# SCH_NFC-Business-Card_2025-01-11.net
KiCad netlist of a schematic drawn in EasyEDA
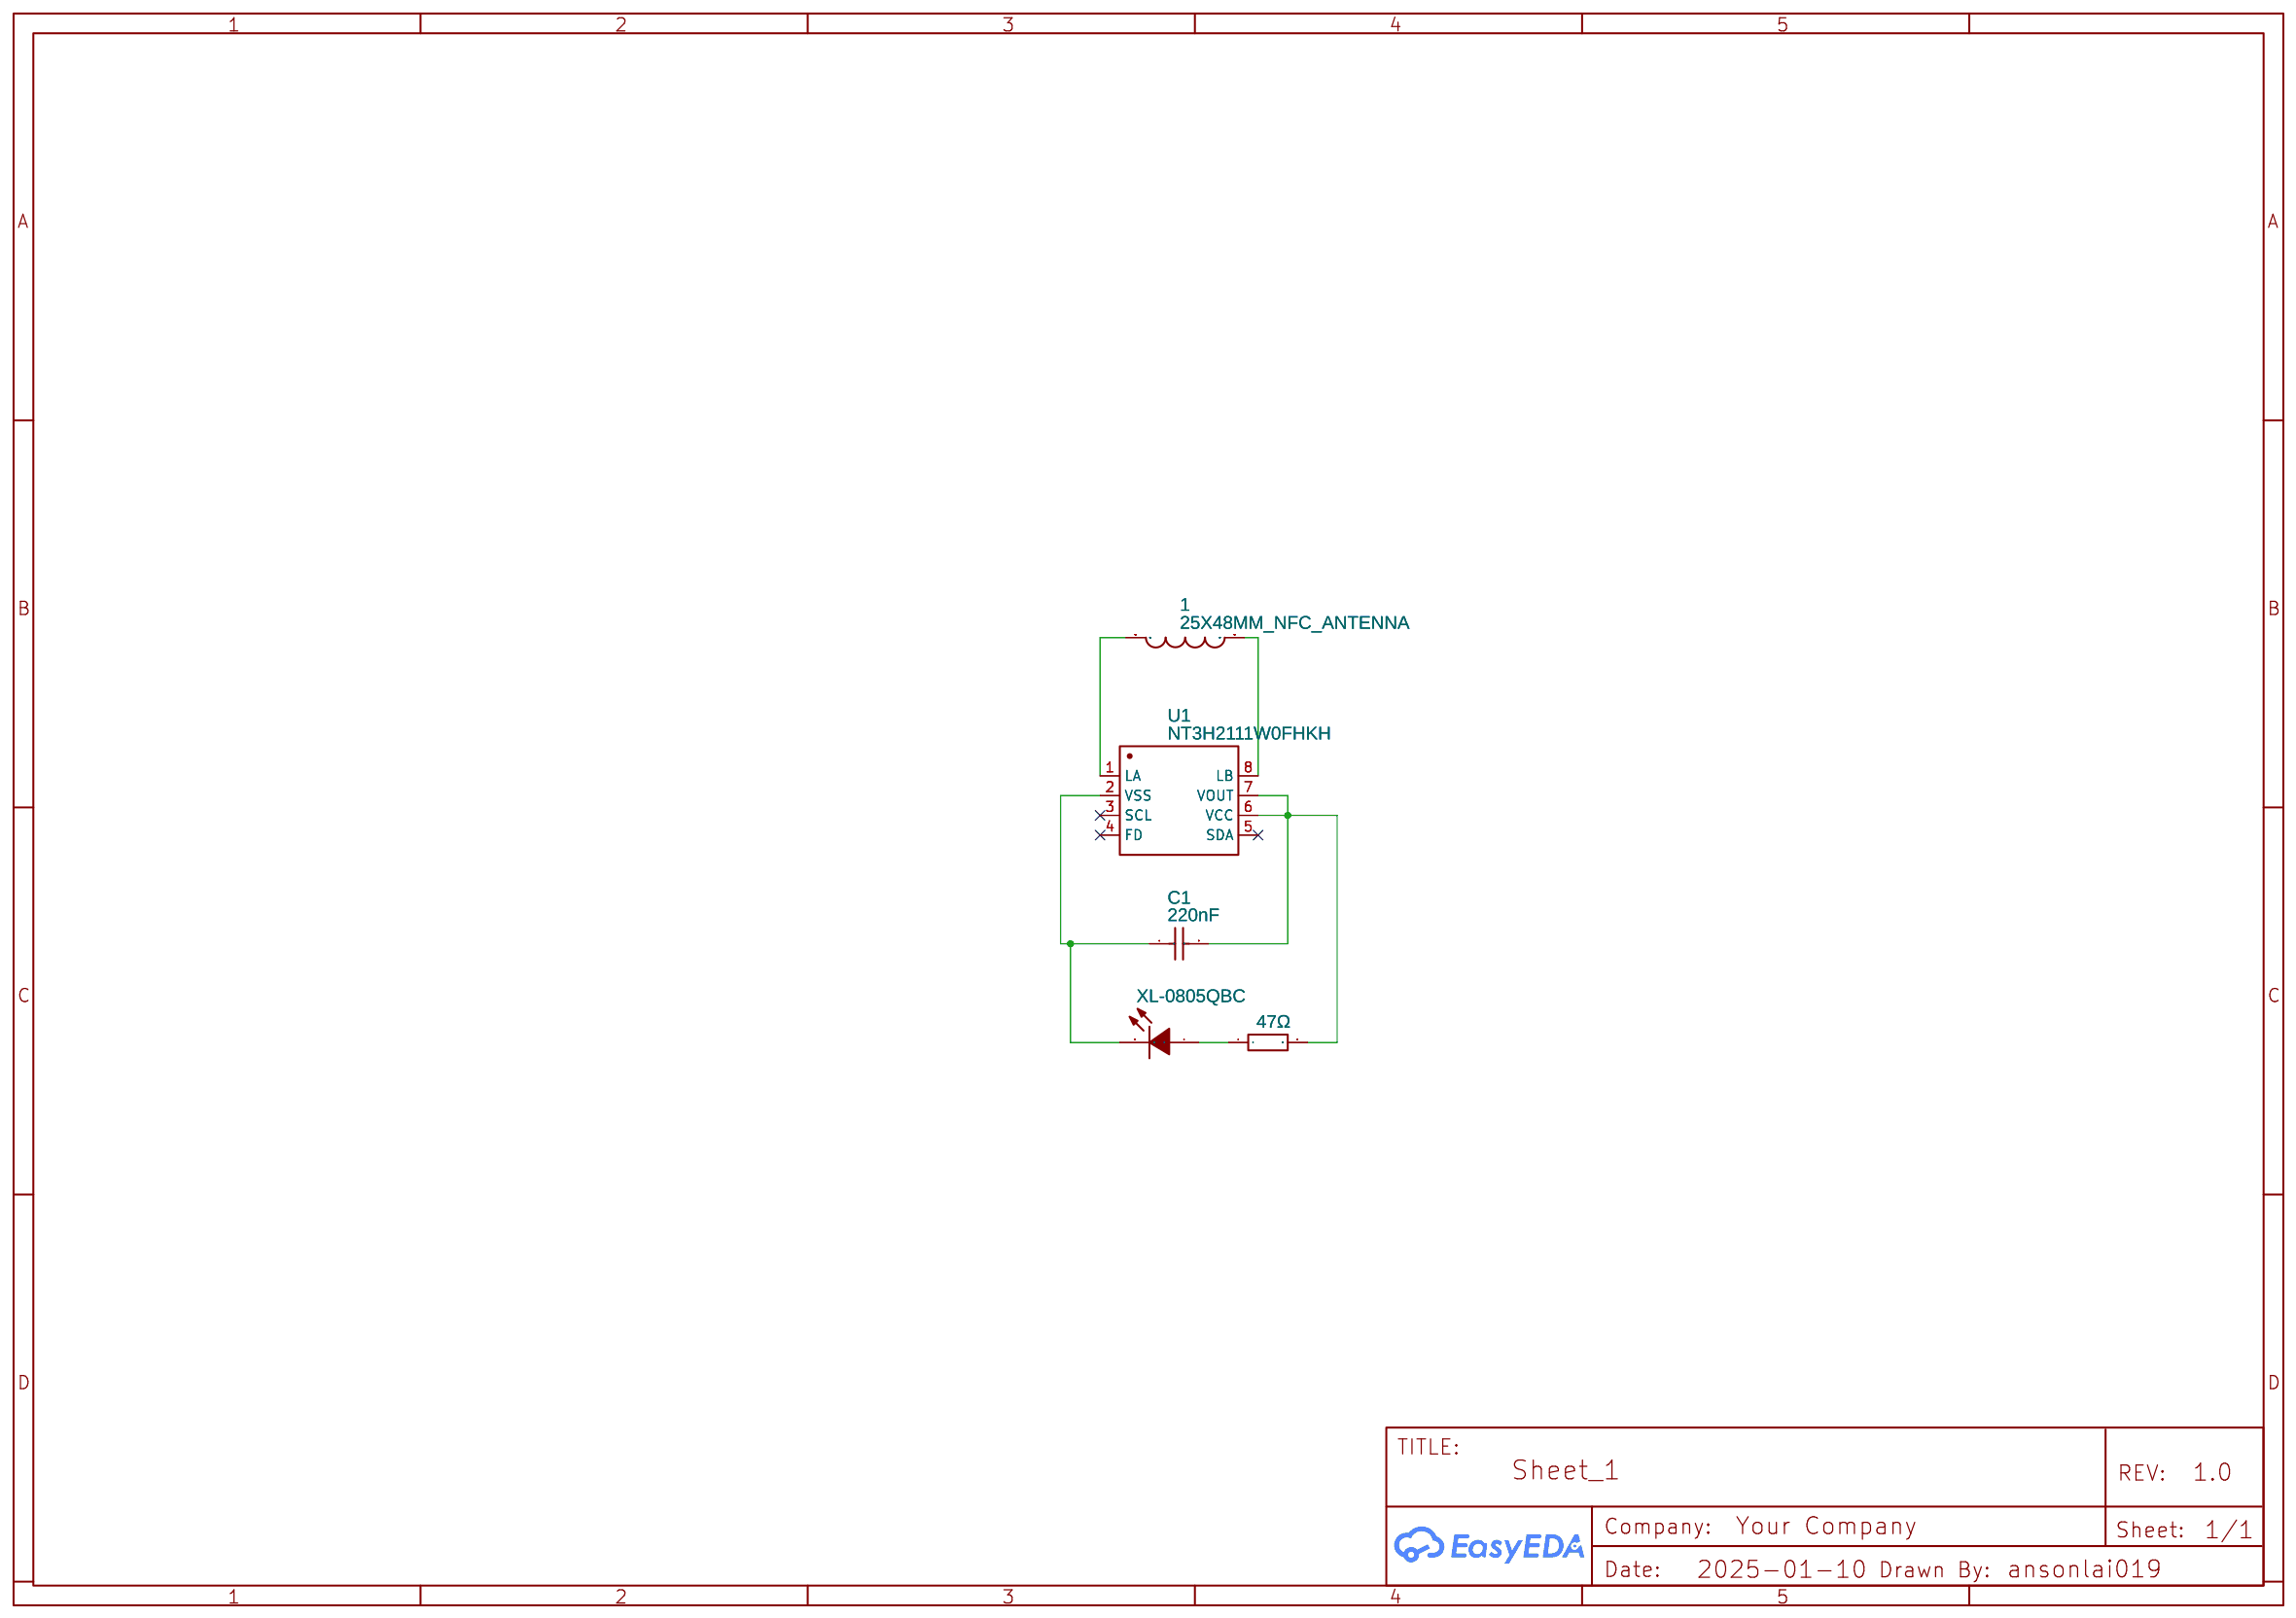
[diagram p0: schematic sheet]

(export (version "E")
  (design (tool "Eeschema 10.0.6"))
  (components
    (comp (ref "1") (value "25X48MM_NFC_ANTENNA") (libsource (lib "") (part "25X48MM_NFC_ANTENNA")))
    (comp (ref "C1")
      (value "220nF")
      (fields
        (field (name "Manufacturer Part") "CL10B224KA8NNNC")
        (field (name "Manufacturer") "SAMSUNG(三星)")
      )
      (libsource (lib "") (part "CL10B224KA8NNNC"))
    )
    (comp (ref "LED1")
      (value "XL-0805QBC")
      (fields (field (name "Manufacturer Part") "KT-0805B") (field (name "Manufacturer") "KENTO"))
      (libsource (lib "") (part "XL-0805QBC"))
    )
    (comp (ref "R1")
      (value "47Ω")
      (fields
        (field (name "Manufacturer Part") "0603WAF470JT5E")
        (field (name "Manufacturer") "UNI-ROYAL(厚声)")
      )
      (libsource (lib "") (part "0603WAF470JT5E"))
    )
    (comp (ref "U1")
      (value "NT3H2111W0FHKH")
      (fields (field (name "Manufacturer") "NXP(恩智浦)"))
      (libsource (lib "") (part "NT3H2111W0FHKH"))
    )
  )
  (nets
    (net (code "1") (name "Net-(LED1-A)") (class "Default")
      (node (ref "LED1") (pin "1") (pinfunction "A_1") (pintype "unspecified"))
      (node (ref "R1") (pin "1") (pinfunction "1_1") (pintype "input"))
    )
    (net (code "2") (name "Net-(LED1-K)") (class "Default")
      (node (ref "C1") (pin "1") (pinfunction "1_1") (pintype "input"))
      (node (ref "LED1") (pin "2") (pinfunction "K_2") (pintype "unspecified"))
      (node (ref "U1") (pin "2") (pinfunction "VSS_2") (pintype "unspecified"))
    )
    (net (code "3") (name "Net-(U1-LA)") (class "Default")
      (node (ref "1") (pin "P$2") (pinfunction "P$2_P$2") (pintype "bidirectional"))
      (node (ref "U1") (pin "1") (pinfunction "LA_1") (pintype "unspecified"))
    )
    (net (code "4") (name "Net-(U1-LB)") (class "Default")
      (node (ref "1") (pin "P$1") (pinfunction "P$1_P$1") (pintype "bidirectional"))
      (node (ref "U1") (pin "8") (pinfunction "LB_8") (pintype "unspecified"))
    )
    (net (code "5") (name "Net-(U1-VCC)") (class "Default")
      (node (ref "C1") (pin "2") (pinfunction "2_2") (pintype "input"))
      (node (ref "R1") (pin "2") (pinfunction "2_2") (pintype "input"))
      (node (ref "U1") (pin "6") (pinfunction "VCC_6") (pintype "unspecified"))
      (node (ref "U1") (pin "7") (pinfunction "VOUT_7") (pintype "unspecified"))
    )
    (net (code "6") (name "unconnected-(U1-FD-Pad4)") (class "Default")
      (node (ref "U1") (pin "4") (pinfunction "FD_4") (pintype "unspecified+no_connect"))
    )
    (net (code "7") (name "unconnected-(U1-SCL-Pad3)") (class "Default")
      (node (ref "U1") (pin "3") (pinfunction "SCL_3") (pintype "unspecified+no_connect"))
    )
    (net (code "8") (name "unconnected-(U1-SDA-Pad5)") (class "Default")
      (node (ref "U1") (pin "5") (pinfunction "SDA_5") (pintype "unspecified+no_connect"))
    )
  )
)
